# UBTB_MIX__spicesch.net
KiCad netlist of a schematic drawn in EAGLE
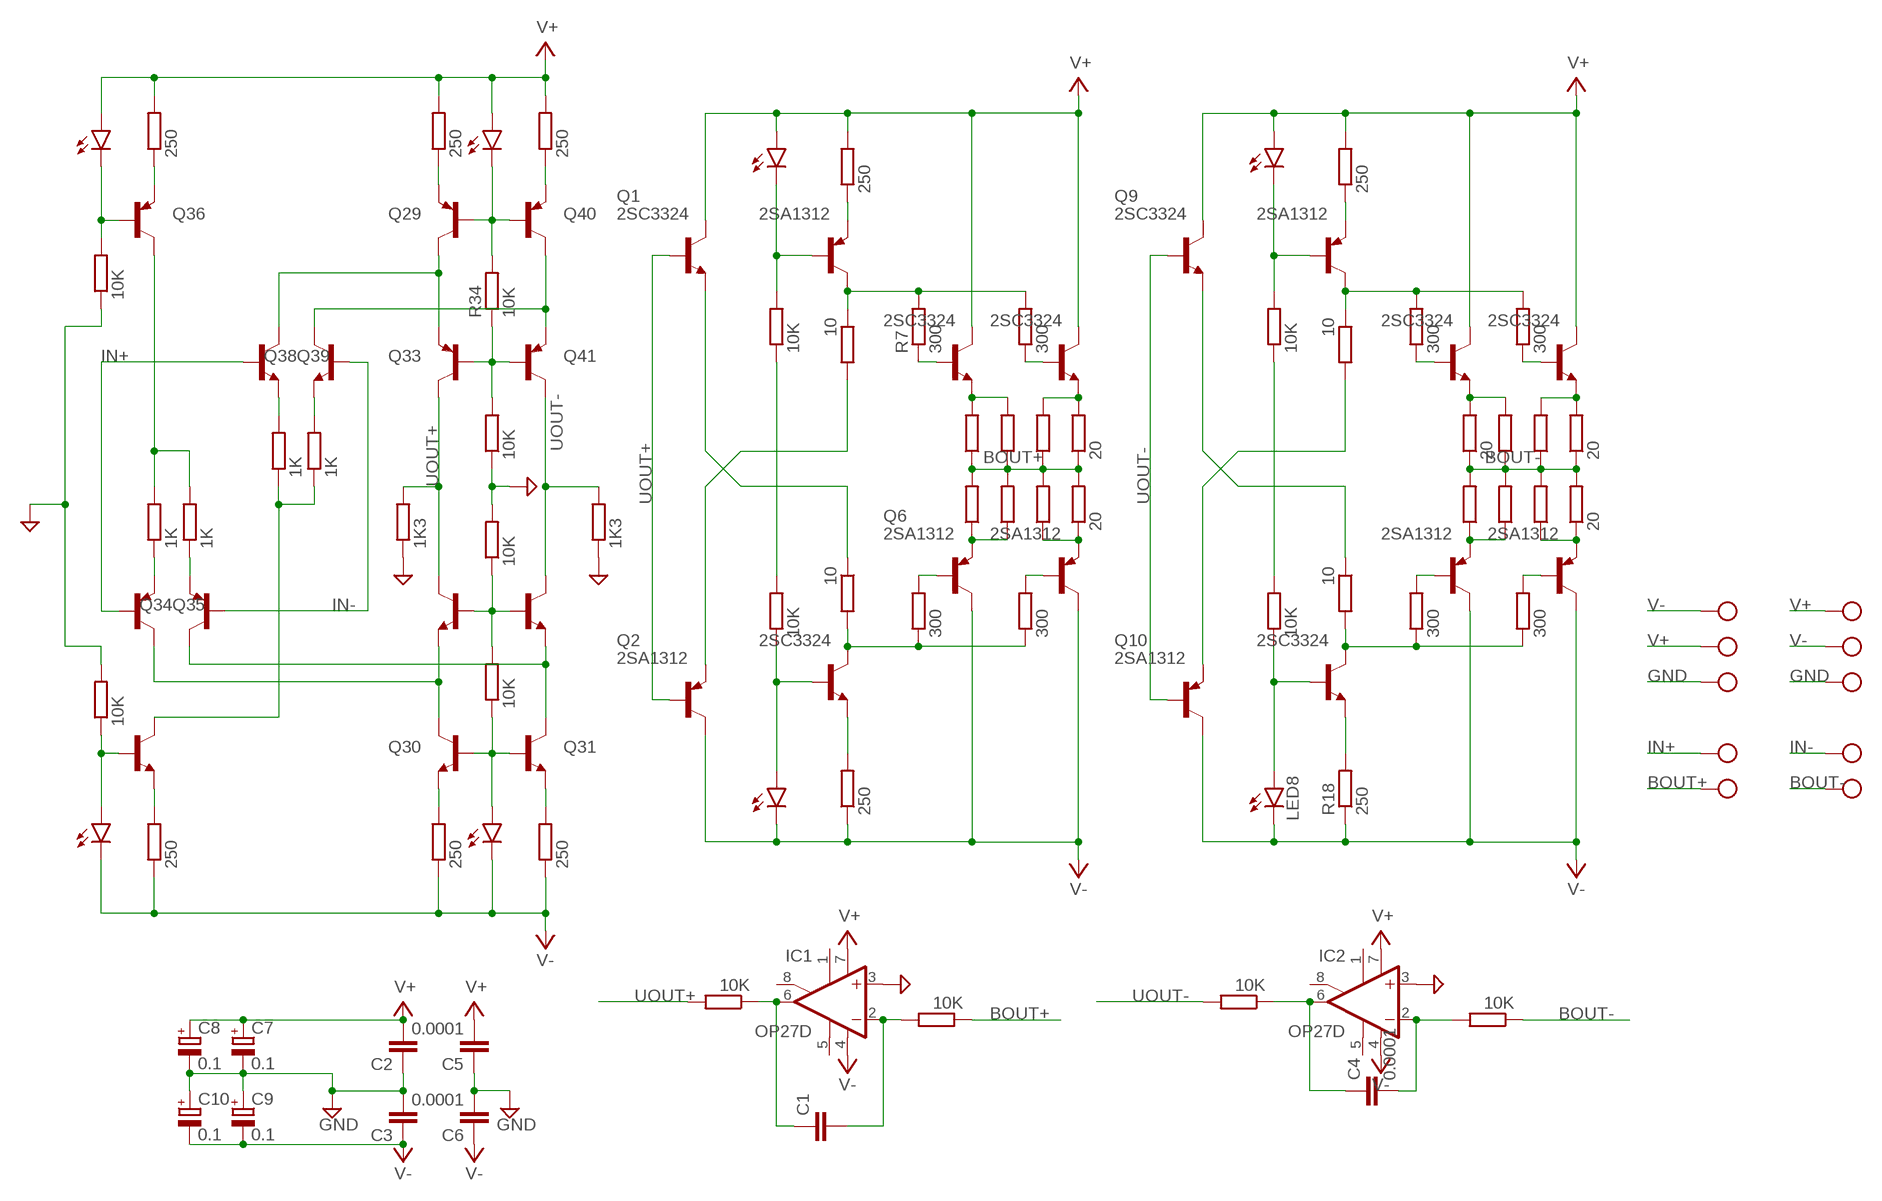
[diagram p0: schematic, sheet 1]

(export (version "E")
  (design (tool "Eeschema 10.0.6"))
  (components
    (comp (ref "C1")
      (value "C-EUC1206")
      (footprint "eagle-import:C1206")
      (fields (field (name "SPICEPREFIX") "C"))
      (libsource (lib "eagle-import") (part "C-EUC1206"))
    )
    (comp (ref "C2")
      (value "C-EUC0805")
      (footprint "eagle-import:C0805")
      (fields (field (name "SPICEPREFIX") "C"))
      (libsource (lib "eagle-import") (part "C-EUC0805"))
    )
    (comp (ref "C3")
      (value "C-EUC0805")
      (footprint "eagle-import:C0805")
      (fields (field (name "SPICEPREFIX") "C"))
      (libsource (lib "eagle-import") (part "C-EUC0805"))
    )
    (comp (ref "C4")
      (value "0.0001")
      (footprint "eagle-import:C1206")
      (fields (field (name "SPICEPREFIX") "C"))
      (libsource (lib "eagle-import") (part "C-EUC1206"))
    )
    (comp (ref "C5")
      (value "0.0001")
      (footprint "eagle-import:C0805")
      (fields (field (name "SPICEPREFIX") "C"))
      (libsource (lib "eagle-import") (part "C-EUC0805"))
    )
    (comp (ref "C6")
      (value "0.0001")
      (footprint "eagle-import:C0805")
      (fields (field (name "SPICEPREFIX") "C"))
      (libsource (lib "eagle-import") (part "C-EUC0805"))
    )
    (comp (ref "C7")
      (value "0.1")
      (footprint "eagle-import:PANASONIC_F")
      (fields (field (name "SPICEPREFIX") "C"))
      (libsource (lib "eagle-import") (part "CPOL-EUF"))
    )
    (comp (ref "C8")
      (value "0.1")
      (footprint "eagle-import:PANASONIC_F")
      (fields (field (name "SPICEPREFIX") "C"))
      (libsource (lib "eagle-import") (part "CPOL-EUF"))
    )
    (comp (ref "C9")
      (value "0.1")
      (footprint "eagle-import:PANASONIC_F")
      (fields (field (name "SPICEPREFIX") "C"))
      (libsource (lib "eagle-import") (part "CPOL-EUF"))
    )
    (comp (ref "C10")
      (value "0.1")
      (footprint "eagle-import:PANASONIC_F")
      (fields (field (name "SPICEPREFIX") "C"))
      (libsource (lib "eagle-import") (part "CPOL-EUF"))
    )
    (comp (ref "IC1")
      (value "OP27D")
      (footprint "eagle-import:SO08")
      (libsource (lib "eagle-import") (part "OP27D"))
    )
    (comp (ref "IC2")
      (value "OP27D")
      (footprint "eagle-import:SO08")
      (libsource (lib "eagle-import") (part "OP27D"))
    )
    (comp (ref "LED1")
      (value "LEDCHIPLED_1206")
      (footprint "eagle-import:CHIPLED_1206")
      (fields (field (name "SPICEPREFIX") "D"))
      (libsource (lib "eagle-import") (part "LEDCHIPLED_1206"))
    )
    (comp (ref "LED2")
      (value "LEDCHIPLED_1206")
      (footprint "eagle-import:CHIPLED_1206")
      (fields (field (name "SPICEPREFIX") "L"))
      (libsource (lib "eagle-import") (part "LEDCHIPLED_1206"))
    )
    (comp (ref "LED3")
      (value "LEDCHIPLED_1206")
      (footprint "eagle-import:CHIPLED_1206")
      (fields (field (name "SPICEPREFIX") "L"))
      (libsource (lib "eagle-import") (part "LEDCHIPLED_1206"))
    )
    (comp (ref "LED4")
      (value "LEDCHIPLED_1206")
      (footprint "eagle-import:CHIPLED_1206")
      (fields (field (name "SPICEPREFIX") "D"))
      (libsource (lib "eagle-import") (part "LEDCHIPLED_1206"))
    )
    (comp (ref "LED5")
      (value "LEDCHIPLED_1206")
      (footprint "eagle-import:CHIPLED_1206")
      (fields (field (name "SPICEPREFIX") "L"))
      (libsource (lib "eagle-import") (part "LEDCHIPLED_1206"))
    )
    (comp (ref "LED6")
      (value "LEDCHIPLED_1206")
      (footprint "eagle-import:CHIPLED_1206")
      (fields (field (name "SPICEPREFIX") "L"))
      (libsource (lib "eagle-import") (part "LEDCHIPLED_1206"))
    )
    (comp (ref "LED7")
      (value "LEDCHIPLED_1206")
      (footprint "eagle-import:CHIPLED_1206")
      (fields (field (name "SPICEPREFIX") "L"))
      (libsource (lib "eagle-import") (part "LEDCHIPLED_1206"))
    )
    (comp (ref "LED8")
      (value "LEDCHIPLED_1206")
      (footprint "eagle-import:CHIPLED_1206")
      (fields (field (name "SPICEPREFIX") "L"))
      (libsource (lib "eagle-import") (part "LEDCHIPLED_1206"))
    )
    (comp (ref "Q1")
      (value "2SC3324")
      (footprint "eagle-import:TRANSISTOR_SOT23-BEC")
      (fields (field (name "SPICEPREFIX") "Q"))
      (libsource (lib "eagle-import") (part "TRANSISTOR_-NPN-SOT23-BECBC846"))
    )
    (comp (ref "Q2")
      (value "2SA1312")
      (footprint "eagle-import:TRANSISTOR_SOT23-BEC")
      (fields (field (name "SPICEPREFIX") "Q"))
      (libsource (lib "eagle-import") (part "TRANSISTOR_-PNP-SOT23-BECBC856B"))
    )
    (comp (ref "Q3")
      (value "2SC3324")
      (footprint "eagle-import:TRANSISTOR_SOT23-BEC")
      (fields (field (name "SPICEPREFIX") "Q"))
      (libsource (lib "eagle-import") (part "TRANSISTOR_-NPN-SOT23-BECBC846"))
    )
    (comp (ref "Q4")
      (value "2SA1312")
      (footprint "eagle-import:TRANSISTOR_SOT23-BEC")
      (fields (field (name "SPICEPREFIX") "Q"))
      (libsource (lib "eagle-import") (part "TRANSISTOR_-PNP-SOT23-BECBC856B"))
    )
    (comp (ref "Q5")
      (value "2SC3324")
      (footprint "eagle-import:TRANSISTOR_SOT23-BEC")
      (fields (field (name "SPICEPREFIX") "Q"))
      (libsource (lib "eagle-import") (part "TRANSISTOR_-NPN-SOT23-BECBC846"))
    )
    (comp (ref "Q6")
      (value "2SA1312")
      (footprint "eagle-import:TRANSISTOR_SOT23-BEC")
      (fields (field (name "SPICEPREFIX") "Q"))
      (libsource (lib "eagle-import") (part "TRANSISTOR_-PNP-SOT23-BECBC856B"))
    )
    (comp (ref "Q7")
      (value "2SA1312")
      (footprint "eagle-import:TRANSISTOR_SOT23-BEC")
      (fields (field (name "SPICEPREFIX") "Q"))
      (libsource (lib "eagle-import") (part "TRANSISTOR_-PNP-SOT23-BECBC856B"))
    )
    (comp (ref "Q8")
      (value "2SC3324")
      (footprint "eagle-import:TRANSISTOR_SOT23-BEC")
      (fields (field (name "SPICEPREFIX") "Q"))
      (libsource (lib "eagle-import") (part "TRANSISTOR_-NPN-SOT23-BECBC846"))
    )
    (comp (ref "Q9")
      (value "2SC3324")
      (footprint "eagle-import:TRANSISTOR_SOT23-BEC")
      (fields (field (name "SPICEPREFIX") "Q"))
      (libsource (lib "eagle-import") (part "TRANSISTOR_-NPN-SOT23-BECBC846"))
    )
    (comp (ref "Q10")
      (value "2SA1312")
      (footprint "eagle-import:TRANSISTOR_SOT23-BEC")
      (fields (field (name "SPICEPREFIX") "Q"))
      (libsource (lib "eagle-import") (part "TRANSISTOR_-PNP-SOT23-BECBC856B"))
    )
    (comp (ref "Q11")
      (value "2SC3324")
      (footprint "eagle-import:TRANSISTOR_SOT23-BEC")
      (fields (field (name "SPICEPREFIX") "Q"))
      (libsource (lib "eagle-import") (part "TRANSISTOR_-NPN-SOT23-BECBC846"))
    )
    (comp (ref "Q12")
      (value "2SA1312")
      (footprint "eagle-import:TRANSISTOR_SOT23-BEC")
      (fields (field (name "SPICEPREFIX") "Q"))
      (libsource (lib "eagle-import") (part "TRANSISTOR_-PNP-SOT23-BECBC856B"))
    )
    (comp (ref "Q13")
      (value "2SC3324")
      (footprint "eagle-import:TRANSISTOR_SOT23-BEC")
      (fields (field (name "SPICEPREFIX") "U"))
      (libsource (lib "eagle-import") (part "TRANSISTOR_-NPN-SOT23-BECBC846"))
    )
    (comp (ref "Q14")
      (value "2SC3324")
      (footprint "eagle-import:TRANSISTOR_SOT23-BEC")
      (fields (field (name "SPICEPREFIX") "Q"))
      (libsource (lib "eagle-import") (part "TRANSISTOR_-NPN-SOT23-BECBC846"))
    )
    (comp (ref "Q15")
      (value "2SA1312")
      (footprint "eagle-import:TRANSISTOR_SOT23-BEC")
      (fields (field (name "SPICEPREFIX") "Q"))
      (libsource (lib "eagle-import") (part "TRANSISTOR_-PNP-SOT23-BECBC856B"))
    )
    (comp (ref "Q16")
      (value "2SA1312")
      (footprint "eagle-import:TRANSISTOR_SOT23-BEC")
      (fields (field (name "SPICEPREFIX") "Q"))
      (libsource (lib "eagle-import") (part "TRANSISTOR_-PNP-SOT23-BECBC856B"))
    )
    (comp (ref "Q26")
      (value "2SC3324")
      (footprint "eagle-import:SOT23")
      (fields (field (name "SPICEPREFIX") "Q"))
      (libsource (lib "eagle-import") (part "BC847SMDC"))
    )
    (comp (ref "Q29")
      (value "2SA1312")
      (footprint "eagle-import:SOT23-BEC")
      (fields (field (name "SPICEPREFIX") "Q"))
      (libsource (lib "eagle-import") (part "BC857SMDC"))
    )
    (comp (ref "Q30")
      (value "2SC3324")
      (footprint "eagle-import:SOT23")
      (fields (field (name "SPICEPREFIX") "Q"))
      (libsource (lib "eagle-import") (part "BC847SMDC"))
    )
    (comp (ref "Q31")
      (value "2SC3324")
      (footprint "eagle-import:SOT23")
      (fields (field (name "SPICEPREFIX") "Q"))
      (libsource (lib "eagle-import") (part "BC847SMDC"))
    )
    (comp (ref "Q32")
      (value "2SC3324")
      (footprint "eagle-import:SOT23")
      (fields (field (name "SPICEPREFIX") "Q"))
      (libsource (lib "eagle-import") (part "BC847SMDC"))
    )
    (comp (ref "Q33")
      (value "2SA1312")
      (footprint "eagle-import:SOT23-BEC")
      (fields (field (name "SPICEPREFIX") "Q"))
      (libsource (lib "eagle-import") (part "BC857SMDC"))
    )
    (comp (ref "Q34")
      (value "2SA1312")
      (footprint "eagle-import:SOT23-BEC")
      (fields (field (name "SPICEPREFIX") "Q"))
      (libsource (lib "eagle-import") (part "BC857SMDC"))
    )
    (comp (ref "Q35")
      (value "2SA1312")
      (footprint "eagle-import:SOT23-BEC")
      (fields (field (name "SPICEPREFIX") "Q"))
      (libsource (lib "eagle-import") (part "BC857SMDC"))
    )
    (comp (ref "Q36")
      (value "2SA1312")
      (footprint "eagle-import:SOT23-BEC")
      (fields (field (name "SPICEPREFIX") "Q"))
      (libsource (lib "eagle-import") (part "BC857SMDC"))
    )
    (comp (ref "Q37")
      (value "2SC3324")
      (footprint "eagle-import:SOT23")
      (fields (field (name "SPICEPREFIX") "Q"))
      (libsource (lib "eagle-import") (part "BC847SMDC"))
    )
    (comp (ref "Q38")
      (value "2SC3324")
      (footprint "eagle-import:SOT23")
      (fields (field (name "SPICEPREFIX") "Q"))
      (libsource (lib "eagle-import") (part "BC847SMDC"))
    )
    (comp (ref "Q39")
      (value "2SC3324")
      (footprint "eagle-import:SOT23")
      (fields (field (name "SPICEPREFIX") "Q"))
      (libsource (lib "eagle-import") (part "BC847SMDC"))
    )
    (comp (ref "Q40")
      (value "2SA1312")
      (footprint "eagle-import:SOT23-BEC")
      (fields (field (name "SPICEPREFIX") "Q"))
      (libsource (lib "eagle-import") (part "BC857SMDC"))
    )
    (comp (ref "Q41")
      (value "2SA1312")
      (footprint "eagle-import:SOT23-BEC")
      (fields (field (name "SPICEPREFIX") "Q"))
      (libsource (lib "eagle-import") (part "BC857SMDC"))
    )
    (comp (ref "R1")
      (value "250")
      (footprint "eagle-import:MINI_MELF-0204W")
      (fields (field (name "SPICEPREFIX") "R"))
      (libsource (lib "eagle-import") (part "R-EU_MELF0204W"))
    )
    (comp (ref "R2")
      (value "250")
      (footprint "eagle-import:MINI_MELF-0204W")
      (fields (field (name "SPICEPREFIX") "R"))
      (libsource (lib "eagle-import") (part "R-EU_MELF0204W"))
    )
    (comp (ref "R3")
      (value "10K")
      (footprint "eagle-import:MINI_MELF-0204W")
      (fields (field (name "SPICEPREFIX") "R"))
      (libsource (lib "eagle-import") (part "R-EU_MELF0204W"))
    )
    (comp (ref "R4")
      (value "10K")
      (footprint "eagle-import:MINI_MELF-0204W")
      (fields (field (name "SPICEPREFIX") "R"))
      (libsource (lib "eagle-import") (part "R-EU_MELF0204W"))
    )
    (comp (ref "R5")
      (value "10")
      (footprint "eagle-import:MINI_MELF-0204W")
      (fields (field (name "SPICEPREFIX") "R"))
      (libsource (lib "eagle-import") (part "R-EU_MELF0204W"))
    )
    (comp (ref "R6")
      (value "10")
      (footprint "eagle-import:MINI_MELF-0204W")
      (fields (field (name "SPICEPREFIX") "R"))
      (libsource (lib "eagle-import") (part "R-EU_MELF0204W"))
    )
    (comp (ref "R7")
      (value "300")
      (footprint "eagle-import:MINI_MELF-0204W")
      (fields (field (name "SPICEPREFIX") "R"))
      (libsource (lib "eagle-import") (part "R-EU_MELF0204W"))
    )
    (comp (ref "R8")
      (value "300")
      (footprint "eagle-import:MINI_MELF-0204W")
      (fields (field (name "SPICEPREFIX") "R"))
      (libsource (lib "eagle-import") (part "R-EU_MELF0204W"))
    )
    (comp (ref "R9")
      (value "300")
      (footprint "eagle-import:MINI_MELF-0204W")
      (fields (field (name "SPICEPREFIX") "R"))
      (libsource (lib "eagle-import") (part "R-EU_MELF0204W"))
    )
    (comp (ref "R10")
      (value "300")
      (footprint "eagle-import:MINI_MELF-0204W")
      (fields (field (name "SPICEPREFIX") "V"))
      (libsource (lib "eagle-import") (part "R-EU_MELF0204W"))
    )
    (comp (ref "R11")
      (value "R-EU_MELF0204W")
      (footprint "eagle-import:MINI_MELF-0204W")
      (fields (field (name "SPICEPREFIX") "R"))
      (libsource (lib "eagle-import") (part "R-EU_MELF0204W"))
    )
    (comp (ref "R12")
      (value "R-EU_MELF0204W")
      (footprint "eagle-import:MINI_MELF-0204W")
      (fields (field (name "SPICEPREFIX") "R"))
      (libsource (lib "eagle-import") (part "R-EU_MELF0204W"))
    )
    (comp (ref "R13")
      (value "20")
      (footprint "eagle-import:MINI_MELF-0204W")
      (fields (field (name "SPICEPREFIX") "R"))
      (libsource (lib "eagle-import") (part "R-EU_MELF0204W"))
    )
    (comp (ref "R14")
      (value "20")
      (footprint "eagle-import:MINI_MELF-0204W")
      (fields (field (name "SPICEPREFIX") "R"))
      (libsource (lib "eagle-import") (part "R-EU_MELF0204W"))
    )
    (comp (ref "R15")
      (value "250")
      (footprint "eagle-import:MINI_MELF-0204W")
      (fields (field (name "SPICEPREFIX") "R"))
      (libsource (lib "eagle-import") (part "R-EU_MELF0204W"))
    )
    (comp (ref "R16")
      (value "10K")
      (footprint "eagle-import:MINI_MELF-0204W")
      (fields (field (name "SPICEPREFIX") "W"))
      (libsource (lib "eagle-import") (part "R-EU_MELF0204W"))
    )
    (comp (ref "R17")
      (value "10K")
      (footprint "eagle-import:MINI_MELF-0204W")
      (fields (field (name "SPICEPREFIX") "R"))
      (libsource (lib "eagle-import") (part "R-EU_MELF0204W"))
    )
    (comp (ref "R18")
      (value "250")
      (footprint "eagle-import:MINI_MELF-0204W")
      (fields (field (name "SPICEPREFIX") "R"))
      (libsource (lib "eagle-import") (part "R-EU_MELF0204W"))
    )
    (comp (ref "R19")
      (value "10K")
      (footprint "eagle-import:MINI_MELF-0204W")
      (fields (field (name "SPICEPREFIX") "R"))
      (libsource (lib "eagle-import") (part "R-EU_MELF0204W"))
    )
    (comp (ref "R20")
      (value "10K")
      (footprint "eagle-import:MINI_MELF-0204W")
      (fields (field (name "SPICEPREFIX") "R"))
      (libsource (lib "eagle-import") (part "R-EU_MELF0204W"))
    )
    (comp (ref "R21")
      (value "10")
      (footprint "eagle-import:MINI_MELF-0204W")
      (fields (field (name "SPICEPREFIX") "R"))
      (libsource (lib "eagle-import") (part "R-EU_MELF0204W"))
    )
    (comp (ref "R22")
      (value "250")
      (footprint "eagle-import:MINI_MELF-0204W")
      (fields (field (name "SPICEPREFIX") "R"))
      (libsource (lib "eagle-import") (part "R-EU_MELF0204W"))
    )
    (comp (ref "R23")
      (value "250")
      (footprint "eagle-import:MINI_MELF-0204W")
      (fields (field (name "SPICEPREFIX") "R"))
      (libsource (lib "eagle-import") (part "R-EU_MELF0204W"))
    )
    (comp (ref "R24")
      (value "10")
      (footprint "eagle-import:MINI_MELF-0204W")
      (fields (field (name "SPICEPREFIX") "W"))
      (libsource (lib "eagle-import") (part "R-EU_MELF0204W"))
    )
    (comp (ref "R25")
      (value "300")
      (footprint "eagle-import:MINI_MELF-0204W")
      (fields (field (name "SPICEPREFIX") "V"))
      (libsource (lib "eagle-import") (part "R-EU_MELF0204W"))
    )
    (comp (ref "R26")
      (value "300")
      (footprint "eagle-import:MINI_MELF-0204W")
      (fields (field (name "SPICEPREFIX") "R"))
      (libsource (lib "eagle-import") (part "R-EU_MELF0204W"))
    )
    (comp (ref "R27")
      (value "300")
      (footprint "eagle-import:MINI_MELF-0204W")
      (fields (field (name "SPICEPREFIX") "V"))
      (libsource (lib "eagle-import") (part "R-EU_MELF0204W"))
    )
    (comp (ref "R28")
      (value "300")
      (footprint "eagle-import:MINI_MELF-0204W")
      (fields (field (name "SPICEPREFIX") "V"))
      (libsource (lib "eagle-import") (part "R-EU_MELF0204W"))
    )
    (comp (ref "R29")
      (value "10K")
      (footprint "eagle-import:MINI_MELF-0204W")
      (fields (field (name "SPICEPREFIX") "R"))
      (libsource (lib "eagle-import") (part "R-EU_MELF0204W"))
    )
    (comp (ref "R30")
      (value "20")
      (footprint "eagle-import:MINI_MELF-0204W")
      (fields (field (name "SPICEPREFIX") "R"))
      (libsource (lib "eagle-import") (part "R-EU_MELF0204W"))
    )
    (comp (ref "R31")
      (value "R-EU_MELF0204W")
      (footprint "eagle-import:MINI_MELF-0204W")
      (fields (field (name "SPICEPREFIX") "R"))
      (libsource (lib "eagle-import") (part "R-EU_MELF0204W"))
    )
    (comp (ref "R32")
      (value "10K")
      (footprint "eagle-import:MINI_MELF-0204W")
      (fields (field (name "SPICEPREFIX") "V"))
      (libsource (lib "eagle-import") (part "R-EU_MELF0204W"))
    )
    (comp (ref "R33")
      (value "10K")
      (footprint "eagle-import:MINI_MELF-0204W")
      (fields (field (name "SPICEPREFIX") "W"))
      (libsource (lib "eagle-import") (part "R-EU_MELF0204W"))
    )
    (comp (ref "R34")
      (value "10K")
      (footprint "eagle-import:MINI_MELF-0204W")
      (fields (field (name "SPICEPREFIX") "R"))
      (libsource (lib "eagle-import") (part "R-EU_MELF0204W"))
    )
    (comp (ref "R35")
      (value "250")
      (footprint "eagle-import:MINI_MELF-0204W")
      (fields (field (name "SPICEPREFIX") "R"))
      (libsource (lib "eagle-import") (part "R-EU_MELF0204W"))
    )
    (comp (ref "R36")
      (value "250")
      (footprint "eagle-import:MINI_MELF-0204W")
      (fields (field (name "SPICEPREFIX") "R"))
      (libsource (lib "eagle-import") (part "R-EU_MELF0204W"))
    )
    (comp (ref "R37")
      (value "1K3")
      (footprint "eagle-import:MINI_MELF-0204W")
      (fields (field (name "SPICEPREFIX") "R"))
      (libsource (lib "eagle-import") (part "R-EU_MELF0204W"))
    )
    (comp (ref "R38")
      (value "1K3")
      (footprint "eagle-import:MINI_MELF-0204W")
      (fields (field (name "SPICEPREFIX") "R"))
      (libsource (lib "eagle-import") (part "R-EU_MELF0204W"))
    )
    (comp (ref "R39")
      (value "1K")
      (footprint "eagle-import:MINI_MELF-0204W")
      (fields (field (name "SPICEPREFIX") "R"))
      (libsource (lib "eagle-import") (part "R-EU_MELF0204W"))
    )
    (comp (ref "R40")
      (value "1K")
      (footprint "eagle-import:MINI_MELF-0204W")
      (fields (field (name "SPICEPREFIX") "R"))
      (libsource (lib "eagle-import") (part "R-EU_MELF0204W"))
    )
    (comp (ref "R41")
      (value "1K")
      (footprint "eagle-import:MINI_MELF-0204W")
      (fields (field (name "SPICEPREFIX") "R"))
      (libsource (lib "eagle-import") (part "R-EU_MELF0204W"))
    )
    (comp (ref "R42")
      (value "1K")
      (footprint "eagle-import:MINI_MELF-0204W")
      (fields (field (name "SPICEPREFIX") "R"))
      (libsource (lib "eagle-import") (part "R-EU_MELF0204W"))
    )
    (comp (ref "R43")
      (value "250")
      (footprint "eagle-import:MINI_MELF-0204W")
      (fields (field (name "SPICEPREFIX") "R"))
      (libsource (lib "eagle-import") (part "R-EU_MELF0204W"))
    )
    (comp (ref "R44")
      (value "250")
      (footprint "eagle-import:MINI_MELF-0204W")
      (fields (field (name "SPICEPREFIX") "R"))
      (libsource (lib "eagle-import") (part "R-EU_MELF0204W"))
    )
    (comp (ref "R45")
      (value "10K")
      (footprint "eagle-import:MINI_MELF-0204W")
      (fields (field (name "SPICEPREFIX") "R"))
      (libsource (lib "eagle-import") (part "R-EU_MELF0204W"))
    )
    (comp (ref "R46")
      (value "10K")
      (footprint "eagle-import:MINI_MELF-0204W")
      (fields (field (name "SPICEPREFIX") "R"))
      (libsource (lib "eagle-import") (part "R-EU_MELF0204W"))
    )
    (comp (ref "R47")
      (value "20")
      (footprint "eagle-import:MINI_MELF-0204W")
      (fields (field (name "SPICEPREFIX") "R"))
      (libsource (lib "eagle-import") (part "R-EU_MELF0204W"))
    )
    (comp (ref "R48")
      (value "10K")
      (footprint "eagle-import:MINI_MELF-0204W")
      (fields (field (name "SPICEPREFIX") "V"))
      (libsource (lib "eagle-import") (part "R-EU_MELF0204W"))
    )
    (comp (ref "R49")
      (value "20")
      (footprint "eagle-import:MINI_MELF-0204W")
      (fields (field (name "SPICEPREFIX") "R"))
      (libsource (lib "eagle-import") (part "R-EU_MELF0204W"))
    )
    (comp (ref "R50")
      (value "R-EU_MELF0204W")
      (footprint "eagle-import:MINI_MELF-0204W")
      (fields (field (name "SPICEPREFIX") "R"))
      (libsource (lib "eagle-import") (part "R-EU_MELF0204W"))
    )
    (comp (ref "R51")
      (value "10K")
      (footprint "eagle-import:MINI_MELF-0204W")
      (fields (field (name "SPICEPREFIX") "R"))
      (libsource (lib "eagle-import") (part "R-EU_MELF0204W"))
    )
    (comp (ref "R52")
      (value "R-EU_MELF0204W")
      (footprint "eagle-import:MINI_MELF-0204W")
      (fields (field (name "SPICEPREFIX") "R"))
      (libsource (lib "eagle-import") (part "R-EU_MELF0204W"))
    )
    (comp (ref "R53")
      (value "R-EU_MELF0204W")
      (footprint "eagle-import:MINI_MELF-0204W")
      (fields (field (name "SPICEPREFIX") "R"))
      (libsource (lib "eagle-import") (part "R-EU_MELF0204W"))
    )
    (comp (ref "R54")
      (value "R-EU_MELF0204W")
      (footprint "eagle-import:MINI_MELF-0204W")
      (fields (field (name "SPICEPREFIX") "R"))
      (libsource (lib "eagle-import") (part "R-EU_MELF0204W"))
    )
    (comp (ref "R55")
      (value "R-EU_MELF0204W")
      (footprint "eagle-import:MINI_MELF-0204W")
      (fields (field (name "SPICEPREFIX") "R"))
      (libsource (lib "eagle-import") (part "R-EU_MELF0204W"))
    )
    (comp (ref "R56")
      (value "R-EU_MELF0204W")
      (footprint "eagle-import:MINI_MELF-0204W")
      (fields (field (name "SPICEPREFIX") "R"))
      (libsource (lib "eagle-import") (part "R-EU_MELF0204W"))
    )
    (comp (ref "R57")
      (value "R-EU_MELF0204W")
      (footprint "eagle-import:MINI_MELF-0204W")
      (fields (field (name "SPICEPREFIX") "R"))
      (libsource (lib "eagle-import") (part "R-EU_MELF0204W"))
    )
    (comp (ref "R58")
      (value "R-EU_MELF0204W")
      (footprint "eagle-import:MINI_MELF-0204W")
      (fields (field (name "SPICEPREFIX") "R"))
      (libsource (lib "eagle-import") (part "R-EU_MELF0204W"))
    )
    (comp (ref "X1")
      (value "CON-PHOENIX-508_MKDSN1,5/3-5,08")
      (footprint "eagle-import:CON-PHOENIX-508_MKDSN1,5_3-5,08")
      (fields (field (name "SPICEPREFIX") "X"))
      (libsource (lib "eagle-import") (part "CON-PHOENIX-508_MKDSN1,5/3-5,08"))
    )
    (comp (ref "X2")
      (value "CON-PHOENIX-508_MKDSN1,5/3-5,08")
      (footprint "eagle-import:CON-PHOENIX-508_MKDSN1,5_3-5,08")
      (fields (field (name "SPICEPREFIX") "X"))
      (libsource (lib "eagle-import") (part "CON-PHOENIX-508_MKDSN1,5/3-5,08"))
    )
    (comp (ref "X3")
      (value "CON-PHOENIX-508_MKDSN1,5/2-5,08")
      (footprint "eagle-import:CON-PHOENIX-508_MKDSN1,5_2-5,08")
      (fields (field (name "SPICEPREFIX") "X"))
      (libsource (lib "eagle-import") (part "CON-PHOENIX-508_MKDSN1,5/2-5,08"))
    )
    (comp (ref "X4")
      (value "CON-PHOENIX-508_MKDSN1,5/2-5,08")
      (footprint "eagle-import:CON-PHOENIX-508_MKDSN1,5_2-5,08")
      (fields (field (name "SPICEPREFIX") "X"))
      (libsource (lib "eagle-import") (part "CON-PHOENIX-508_MKDSN1,5/2-5,08"))
    )
  )
  (nets
    (net (code "1") (name "/BOUT+") (class "Default")
      (node (ref "R11") (pin "1") (pinfunction "1_1") (pintype "passive"))
      (node (ref "R12") (pin "2") (pinfunction "2_2") (pintype "passive"))
      (node (ref "R13") (pin "1") (pinfunction "1_1") (pintype "passive"))
      (node (ref "R14") (pin "2") (pinfunction "2_2") (pintype "passive"))
      (node (ref "R17") (pin "1") (pinfunction "1_1") (pintype "passive"))
      (node (ref "R50") (pin "1") (pinfunction "1_1") (pintype "passive"))
      (node (ref "R52") (pin "1") (pinfunction "1_1") (pintype "passive"))
      (node (ref "R53") (pin "2") (pinfunction "2_2") (pintype "passive"))
      (node (ref "R54") (pin "2") (pinfunction "2_2") (pintype "passive"))
      (node (ref "X3") (pin "2") (pinfunction "KL_2") (pintype "passive"))
    )
    (net (code "2") (name "/BOUT-") (class "Default")
      (node (ref "R30") (pin "1") (pinfunction "1_1") (pintype "passive"))
      (node (ref "R31") (pin "2") (pinfunction "2_2") (pintype "passive"))
      (node (ref "R47") (pin "1") (pinfunction "1_1") (pintype "passive"))
      (node (ref "R48") (pin "1") (pinfunction "1_1") (pintype "passive"))
      (node (ref "R49") (pin "2") (pinfunction "2_2") (pintype "passive"))
      (node (ref "R55") (pin "1") (pinfunction "1_1") (pintype "passive"))
      (node (ref "R56") (pin "1") (pinfunction "1_1") (pintype "passive"))
      (node (ref "R57") (pin "2") (pinfunction "2_2") (pintype "passive"))
      (node (ref "R58") (pin "2") (pinfunction "2_2") (pintype "passive"))
      (node (ref "X4") (pin "2") (pinfunction "KL_2") (pintype "passive"))
    )
    (net (code "3") (name "/IN+") (class "Default")
      (node (ref "Q35") (pin "B") (pinfunction "B_B") (pintype "passive"))
      (node (ref "Q39") (pin "1") (pinfunction "B_1") (pintype "passive"))
      (node (ref "X3") (pin "1") (pinfunction "KL_1") (pintype "passive"))
    )
    (net (code "4") (name "/IN-") (class "Default")
      (node (ref "Q34") (pin "B") (pinfunction "B_B") (pintype "passive"))
      (node (ref "Q38") (pin "1") (pinfunction "B_1") (pintype "passive"))
      (node (ref "X4") (pin "1") (pinfunction "KL_1") (pintype "passive"))
    )
    (net (code "5") (name "/UOUT+") (class "Default")
      (node (ref "Q1") (pin "B") (pinfunction "B_B") (pintype "passive"))
      (node (ref "Q2") (pin "B") (pinfunction "B_B") (pintype "passive"))
      (node (ref "Q33") (pin "C") (pinfunction "C_C") (pintype "passive"))
      (node (ref "Q37") (pin "3") (pinfunction "C_3") (pintype "passive"))
      (node (ref "R16") (pin "2") (pinfunction "2_2") (pintype "passive"))
      (node (ref "R37") (pin "2") (pinfunction "2_2") (pintype "passive"))
    )
    (net (code "6") (name "/UOUT-") (class "Default")
      (node (ref "Q10") (pin "B") (pinfunction "B_B") (pintype "passive"))
      (node (ref "Q32") (pin "3") (pinfunction "C_3") (pintype "passive"))
      (node (ref "Q41") (pin "C") (pinfunction "C_C") (pintype "passive"))
      (node (ref "Q9") (pin "B") (pinfunction "B_B") (pintype "passive"))
      (node (ref "R38") (pin "2") (pinfunction "2_2") (pintype "passive"))
      (node (ref "R51") (pin "2") (pinfunction "2_2") (pintype "passive"))
    )
    (net (code "7") (name "GND") (class "Default")
      (node (ref "C10") (pin "+") (pinfunction "+_+") (pintype "passive"))
      (node (ref "C2") (pin "1") (pinfunction "1_1") (pintype "passive"))
      (node (ref "C3") (pin "2") (pinfunction "2_2") (pintype "passive"))
      (node (ref "C5") (pin "1") (pinfunction "1_1") (pintype "passive"))
      (node (ref "C6") (pin "2") (pinfunction "2_2") (pintype "passive"))
      (node (ref "C7") (pin "-") (pinfunction "-_-") (pintype "passive"))
      (node (ref "C8") (pin "-") (pinfunction "-_-") (pintype "passive"))
      (node (ref "C9") (pin "+") (pinfunction "+_+") (pintype "passive"))
      (node (ref "IC1") (pin "3") (pinfunction "+IN_3") (pintype "input"))
      (node (ref "IC2") (pin "3") (pinfunction "+IN_3") (pintype "input"))
      (node (ref "R32") (pin "2") (pinfunction "2_2") (pintype "passive"))
      (node (ref "R33") (pin "1") (pinfunction "1_1") (pintype "passive"))
      (node (ref "R37") (pin "1") (pinfunction "1_1") (pintype "passive"))
      (node (ref "R38") (pin "1") (pinfunction "1_1") (pintype "passive"))
      (node (ref "R45") (pin "1") (pinfunction "1_1") (pintype "passive"))
      (node (ref "R46") (pin "2") (pinfunction "2_2") (pintype "passive"))
      (node (ref "X1") (pin "3") (pinfunction "KL_3") (pintype "passive"))
      (node (ref "X2") (pin "3") (pinfunction "KL_3") (pintype "passive"))
    )
    (net (code "8") (name "Net-(IC1--IN)") (class "Default")
      (node (ref "C1") (pin "2") (pinfunction "2_2") (pintype "passive"))
      (node (ref "IC1") (pin "2") (pinfunction "-IN_2") (pintype "input"))
      (node (ref "R17") (pin "2") (pinfunction "2_2") (pintype "passive"))
    )
    (net (code "9") (name "Net-(IC1-OUT)") (class "Default")
      (node (ref "C1") (pin "1") (pinfunction "1_1") (pintype "passive"))
      (node (ref "IC1") (pin "6") (pinfunction "OUT_6") (pintype "output"))
      (node (ref "R16") (pin "1") (pinfunction "1_1") (pintype "passive"))
    )
    (net (code "10") (name "Net-(IC2--IN)") (class "Default")
      (node (ref "C4") (pin "2") (pinfunction "2_2") (pintype "passive"))
      (node (ref "IC2") (pin "2") (pinfunction "-IN_2") (pintype "input"))
      (node (ref "R48") (pin "2") (pinfunction "2_2") (pintype "passive"))
    )
    (net (code "11") (name "Net-(IC2-OUT)") (class "Default")
      (node (ref "C4") (pin "1") (pinfunction "1_1") (pintype "passive"))
      (node (ref "IC2") (pin "6") (pinfunction "OUT_6") (pintype "output"))
      (node (ref "R51") (pin "1") (pinfunction "1_1") (pintype "passive"))
    )
    (net (code "12") (name "Net-(LED2-PadC)") (class "Default")
      (node (ref "LED2") (pin "C") (pinfunction "C_C") (pintype "passive"))
      (node (ref "Q29") (pin "B") (pinfunction "B_B") (pintype "passive"))
      (node (ref "Q40") (pin "B") (pinfunction "B_B") (pintype "passive"))
      (node (ref "R34") (pin "2") (pinfunction "2_2") (pintype "passive"))
    )
    (net (code "13") (name "Net-(LED3-PadC)") (class "Default")
      (node (ref "LED3") (pin "C") (pinfunction "C_C") (pintype "passive"))
      (node (ref "Q36") (pin "B") (pinfunction "B_B") (pintype "passive"))
      (node (ref "R45") (pin "2") (pinfunction "2_2") (pintype "passive"))
    )
    (net (code "14") (name "Net-(LED5-PadC)") (class "Default")
      (node (ref "LED5") (pin "C") (pinfunction "C_C") (pintype "passive"))
      (node (ref "Q4") (pin "B") (pinfunction "B_B") (pintype "passive"))
      (node (ref "R3") (pin "2") (pinfunction "2_2") (pintype "passive"))
    )
    (net (code "15") (name "Net-(LED6-PadA)") (class "Default")
      (node (ref "LED6") (pin "A") (pinfunction "A_A") (pintype "passive"))
      (node (ref "Q3") (pin "B") (pinfunction "B_B") (pintype "passive"))
      (node (ref "R4") (pin "1") (pinfunction "1_1") (pintype "passive"))
    )
    (net (code "16") (name "Net-(LED7-PadC)") (class "Default")
      (node (ref "LED7") (pin "C") (pinfunction "C_C") (pintype "passive"))
      (node (ref "Q12") (pin "B") (pinfunction "B_B") (pintype "passive"))
      (node (ref "R19") (pin "2") (pinfunction "2_2") (pintype "passive"))
    )
    (net (code "17") (name "Net-(LED8-PadA)") (class "Default")
      (node (ref "LED8") (pin "A") (pinfunction "A_A") (pintype "passive"))
      (node (ref "Q11") (pin "B") (pinfunction "B_B") (pintype "passive"))
      (node (ref "R20") (pin "1") (pinfunction "1_1") (pintype "passive"))
    )
    (net (code "18") (name "Net-(Q1-PadE)") (class "Default")
      (node (ref "Q1") (pin "E") (pinfunction "E_E") (pintype "passive"))
      (node (ref "R6") (pin "1") (pinfunction "1_1") (pintype "passive"))
    )
    (net (code "19") (name "Net-(Q2-PadE)") (class "Default")
      (node (ref "Q2") (pin "E") (pinfunction "E_E") (pintype "passive"))
      (node (ref "R5") (pin "2") (pinfunction "2_2") (pintype "passive"))
    )
    (net (code "20") (name "Net-(Q3-PadC)") (class "Default")
      (node (ref "Q3") (pin "C") (pinfunction "C_C") (pintype "passive"))
      (node (ref "R6") (pin "2") (pinfunction "2_2") (pintype "passive"))
      (node (ref "R8") (pin "1") (pinfunction "1_1") (pintype "passive"))
      (node (ref "R9") (pin "1") (pinfunction "1_1") (pintype "passive"))
    )
    (net (code "21") (name "Net-(Q3-PadE)") (class "Default")
      (node (ref "Q3") (pin "E") (pinfunction "E_E") (pintype "passive"))
      (node (ref "R2") (pin "2") (pinfunction "2_2") (pintype "passive"))
    )
    (net (code "22") (name "Net-(Q4-PadC)") (class "Default")
      (node (ref "Q4") (pin "C") (pinfunction "C_C") (pintype "passive"))
      (node (ref "R10") (pin "2") (pinfunction "2_2") (pintype "passive"))
      (node (ref "R5") (pin "1") (pinfunction "1_1") (pintype "passive"))
      (node (ref "R7") (pin "2") (pinfunction "2_2") (pintype "passive"))
    )
    (net (code "23") (name "Net-(Q4-PadE)") (class "Default")
      (node (ref "Q4") (pin "E") (pinfunction "E_E") (pintype "passive"))
      (node (ref "R1") (pin "1") (pinfunction "1_1") (pintype "passive"))
    )
    (net (code "24") (name "Net-(Q5-PadB)") (class "Default")
      (node (ref "Q5") (pin "B") (pinfunction "B_B") (pintype "passive"))
      (node (ref "R7") (pin "1") (pinfunction "1_1") (pintype "passive"))
    )
    (net (code "25") (name "Net-(Q5-PadE)") (class "Default")
      (node (ref "Q5") (pin "E") (pinfunction "E_E") (pintype "passive"))
      (node (ref "R11") (pin "2") (pinfunction "2_2") (pintype "passive"))
      (node (ref "R50") (pin "2") (pinfunction "2_2") (pintype "passive"))
    )
    (net (code "26") (name "Net-(Q6-PadB)") (class "Default")
      (node (ref "Q6") (pin "B") (pinfunction "B_B") (pintype "passive"))
      (node (ref "R8") (pin "2") (pinfunction "2_2") (pintype "passive"))
    )
    (net (code "27") (name "Net-(Q6-PadE)") (class "Default")
      (node (ref "Q6") (pin "E") (pinfunction "E_E") (pintype "passive"))
      (node (ref "R12") (pin "1") (pinfunction "1_1") (pintype "passive"))
      (node (ref "R53") (pin "1") (pinfunction "1_1") (pintype "passive"))
    )
    (net (code "28") (name "Net-(Q7-PadB)") (class "Default")
      (node (ref "Q7") (pin "B") (pinfunction "B_B") (pintype "passive"))
      (node (ref "R9") (pin "2") (pinfunction "2_2") (pintype "passive"))
    )
    (net (code "29") (name "Net-(Q7-PadE)") (class "Default")
      (node (ref "Q7") (pin "E") (pinfunction "E_E") (pintype "passive"))
      (node (ref "R14") (pin "1") (pinfunction "1_1") (pintype "passive"))
      (node (ref "R54") (pin "1") (pinfunction "1_1") (pintype "passive"))
    )
    (net (code "30") (name "Net-(Q8-PadB)") (class "Default")
      (node (ref "Q8") (pin "B") (pinfunction "B_B") (pintype "passive"))
      (node (ref "R10") (pin "1") (pinfunction "1_1") (pintype "passive"))
    )
    (net (code "31") (name "Net-(Q8-PadE)") (class "Default")
      (node (ref "Q8") (pin "E") (pinfunction "E_E") (pintype "passive"))
      (node (ref "R13") (pin "2") (pinfunction "2_2") (pintype "passive"))
      (node (ref "R52") (pin "2") (pinfunction "2_2") (pintype "passive"))
    )
    (net (code "32") (name "Net-(Q9-PadE)") (class "Default")
      (node (ref "Q9") (pin "E") (pinfunction "E_E") (pintype "passive"))
      (node (ref "R24") (pin "1") (pinfunction "1_1") (pintype "passive"))
    )
    (net (code "33") (name "Net-(Q10-PadE)") (class "Default")
      (node (ref "Q10") (pin "E") (pinfunction "E_E") (pintype "passive"))
      (node (ref "R21") (pin "2") (pinfunction "2_2") (pintype "passive"))
    )
    (net (code "34") (name "Net-(Q11-PadC)") (class "Default")
      (node (ref "Q11") (pin "C") (pinfunction "C_C") (pintype "passive"))
      (node (ref "R24") (pin "2") (pinfunction "2_2") (pintype "passive"))
      (node (ref "R26") (pin "1") (pinfunction "1_1") (pintype "passive"))
      (node (ref "R27") (pin "1") (pinfunction "1_1") (pintype "passive"))
    )
    (net (code "35") (name "Net-(Q11-PadE)") (class "Default")
      (node (ref "Q11") (pin "E") (pinfunction "E_E") (pintype "passive"))
      (node (ref "R18") (pin "2") (pinfunction "2_2") (pintype "passive"))
    )
    (net (code "36") (name "Net-(Q12-PadC)") (class "Default")
      (node (ref "Q12") (pin "C") (pinfunction "C_C") (pintype "passive"))
      (node (ref "R21") (pin "1") (pinfunction "1_1") (pintype "passive"))
      (node (ref "R25") (pin "2") (pinfunction "2_2") (pintype "passive"))
      (node (ref "R28") (pin "2") (pinfunction "2_2") (pintype "passive"))
    )
    (net (code "37") (name "Net-(Q12-PadE)") (class "Default")
      (node (ref "Q12") (pin "E") (pinfunction "E_E") (pintype "passive"))
      (node (ref "R15") (pin "1") (pinfunction "1_1") (pintype "passive"))
    )
    (net (code "38") (name "Net-(Q13-PadB)") (class "Default")
      (node (ref "Q13") (pin "B") (pinfunction "B_B") (pintype "passive"))
      (node (ref "R25") (pin "1") (pinfunction "1_1") (pintype "passive"))
    )
    (net (code "39") (name "Net-(Q13-PadE)") (class "Default")
      (node (ref "Q13") (pin "E") (pinfunction "E_E") (pintype "passive"))
      (node (ref "R30") (pin "2") (pinfunction "2_2") (pintype "passive"))
      (node (ref "R55") (pin "2") (pinfunction "2_2") (pintype "passive"))
    )
    (net (code "40") (name "Net-(Q14-PadB)") (class "Default")
      (node (ref "Q14") (pin "B") (pinfunction "B_B") (pintype "passive"))
      (node (ref "R28") (pin "1") (pinfunction "1_1") (pintype "passive"))
    )
    (net (code "41") (name "Net-(Q14-PadE)") (class "Default")
      (node (ref "Q14") (pin "E") (pinfunction "E_E") (pintype "passive"))
      (node (ref "R47") (pin "2") (pinfunction "2_2") (pintype "passive"))
      (node (ref "R56") (pin "2") (pinfunction "2_2") (pintype "passive"))
    )
    (net (code "42") (name "Net-(Q15-PadB)") (class "Default")
      (node (ref "Q15") (pin "B") (pinfunction "B_B") (pintype "passive"))
      (node (ref "R26") (pin "2") (pinfunction "2_2") (pintype "passive"))
    )
    (net (code "43") (name "Net-(Q15-PadE)") (class "Default")
      (node (ref "Q15") (pin "E") (pinfunction "E_E") (pintype "passive"))
      (node (ref "R31") (pin "1") (pinfunction "1_1") (pintype "passive"))
      (node (ref "R58") (pin "1") (pinfunction "1_1") (pintype "passive"))
    )
    (net (code "44") (name "Net-(Q16-PadB)") (class "Default")
      (node (ref "Q16") (pin "B") (pinfunction "B_B") (pintype "passive"))
      (node (ref "R27") (pin "2") (pinfunction "2_2") (pintype "passive"))
    )
    (net (code "45") (name "Net-(Q16-PadE)") (class "Default")
      (node (ref "Q16") (pin "E") (pinfunction "E_E") (pintype "passive"))
      (node (ref "R49") (pin "1") (pinfunction "1_1") (pintype "passive"))
      (node (ref "R57") (pin "1") (pinfunction "1_1") (pintype "passive"))
    )
    (net (code "46") (name "Net-(Q26-B)") (class "Default")
      (node (ref "LED4") (pin "A") (pinfunction "A_A") (pintype "passive"))
      (node (ref "Q26") (pin "1") (pinfunction "B_1") (pintype "passive"))
      (node (ref "R46") (pin "1") (pinfunction "1_1") (pintype "passive"))
    )
    (net (code "47") (name "Net-(Q26-C)") (class "Default")
      (node (ref "Q26") (pin "3") (pinfunction "C_3") (pintype "passive"))
      (node (ref "R39") (pin "1") (pinfunction "1_1") (pintype "passive"))
      (node (ref "R40") (pin "1") (pinfunction "1_1") (pintype "passive"))
    )
    (net (code "48") (name "Net-(Q26-E)") (class "Default")
      (node (ref "Q26") (pin "2") (pinfunction "E_2") (pintype "passive"))
      (node (ref "R44") (pin "2") (pinfunction "2_2") (pintype "passive"))
    )
    (net (code "49") (name "Net-(Q29-PadE)") (class "Default")
      (node (ref "Q29") (pin "E") (pinfunction "E_E") (pintype "passive"))
      (node (ref "R35") (pin "1") (pinfunction "1_1") (pintype "passive"))
    )
    (net (code "50") (name "Net-(Q30-B)") (class "Default")
      (node (ref "LED1") (pin "A") (pinfunction "A_A") (pintype "passive"))
      (node (ref "Q30") (pin "1") (pinfunction "B_1") (pintype "passive"))
      (node (ref "Q31") (pin "1") (pinfunction "B_1") (pintype "passive"))
      (node (ref "R29") (pin "1") (pinfunction "1_1") (pintype "passive"))
    )
    (net (code "51") (name "Net-(Q30-C)") (class "Default")
      (node (ref "Q30") (pin "3") (pinfunction "C_3") (pintype "passive"))
      (node (ref "Q35") (pin "C") (pinfunction "C_C") (pintype "passive"))
      (node (ref "Q37") (pin "2") (pinfunction "E_2") (pintype "passive"))
    )
    (net (code "52") (name "Net-(Q30-E)") (class "Default")
      (node (ref "Q30") (pin "2") (pinfunction "E_2") (pintype "passive"))
      (node (ref "R22") (pin "2") (pinfunction "2_2") (pintype "passive"))
    )
    (net (code "53") (name "Net-(Q31-C)") (class "Default")
      (node (ref "Q31") (pin "3") (pinfunction "C_3") (pintype "passive"))
      (node (ref "Q32") (pin "2") (pinfunction "E_2") (pintype "passive"))
      (node (ref "Q34") (pin "C") (pinfunction "C_C") (pintype "passive"))
    )
    (net (code "54") (name "Net-(Q31-E)") (class "Default")
      (node (ref "Q31") (pin "2") (pinfunction "E_2") (pintype "passive"))
      (node (ref "R23") (pin "2") (pinfunction "2_2") (pintype "passive"))
    )
    (net (code "55") (name "Net-(Q32-B)") (class "Default")
      (node (ref "Q32") (pin "1") (pinfunction "B_1") (pintype "passive"))
      (node (ref "Q37") (pin "1") (pinfunction "B_1") (pintype "passive"))
      (node (ref "R29") (pin "2") (pinfunction "2_2") (pintype "passive"))
      (node (ref "R32") (pin "1") (pinfunction "1_1") (pintype "passive"))
    )
    (net (code "56") (name "Net-(Q33-PadB)") (class "Default")
      (node (ref "Q33") (pin "B") (pinfunction "B_B") (pintype "passive"))
      (node (ref "Q41") (pin "B") (pinfunction "B_B") (pintype "passive"))
      (node (ref "R33") (pin "2") (pinfunction "2_2") (pintype "passive"))
      (node (ref "R34") (pin "1") (pinfunction "1_1") (pintype "passive"))
    )
    (net (code "57") (name "Net-(Q34-PadE)") (class "Default")
      (node (ref "Q34") (pin "E") (pinfunction "E_E") (pintype "passive"))
      (node (ref "R42") (pin "1") (pinfunction "1_1") (pintype "passive"))
    )
    (net (code "58") (name "Net-(Q35-PadE)") (class "Default")
      (node (ref "Q35") (pin "E") (pinfunction "E_E") (pintype "passive"))
      (node (ref "R41") (pin "1") (pinfunction "1_1") (pintype "passive"))
    )
    (net (code "59") (name "Net-(Q36-PadC)") (class "Default")
      (node (ref "Q36") (pin "C") (pinfunction "C_C") (pintype "passive"))
      (node (ref "R41") (pin "2") (pinfunction "2_2") (pintype "passive"))
      (node (ref "R42") (pin "2") (pinfunction "2_2") (pintype "passive"))
    )
    (net (code "60") (name "Net-(Q36-PadE)") (class "Default")
      (node (ref "Q36") (pin "E") (pinfunction "E_E") (pintype "passive"))
      (node (ref "R43") (pin "1") (pinfunction "1_1") (pintype "passive"))
    )
    (net (code "61") (name "Net-(Q38-C)") (class "Default")
      (node (ref "Q38") (pin "3") (pinfunction "C_3") (pintype "passive"))
      (node (ref "Q40") (pin "C") (pinfunction "C_C") (pintype "passive"))
      (node (ref "Q41") (pin "E") (pinfunction "E_E") (pintype "passive"))
    )
    (net (code "62") (name "Net-(Q38-E)") (class "Default")
      (node (ref "Q38") (pin "2") (pinfunction "E_2") (pintype "passive"))
      (node (ref "R40") (pin "2") (pinfunction "2_2") (pintype "passive"))
    )
    (net (code "63") (name "Net-(Q39-C)") (class "Default")
      (node (ref "Q29") (pin "C") (pinfunction "C_C") (pintype "passive"))
      (node (ref "Q33") (pin "E") (pinfunction "E_E") (pintype "passive"))
      (node (ref "Q39") (pin "3") (pinfunction "C_3") (pintype "passive"))
    )
    (net (code "64") (name "Net-(Q39-E)") (class "Default")
      (node (ref "Q39") (pin "2") (pinfunction "E_2") (pintype "passive"))
      (node (ref "R39") (pin "2") (pinfunction "2_2") (pintype "passive"))
    )
    (net (code "65") (name "Net-(Q40-PadE)") (class "Default")
      (node (ref "Q40") (pin "E") (pinfunction "E_E") (pintype "passive"))
      (node (ref "R36") (pin "1") (pinfunction "1_1") (pintype "passive"))
    )
    (net (code "66") (name "Net-(R3-Pad1)") (class "Default")
      (node (ref "R3") (pin "1") (pinfunction "1_1") (pintype "passive"))
      (node (ref "R4") (pin "2") (pinfunction "2_2") (pintype "passive"))
    )
    (net (code "67") (name "Net-(R19-Pad1)") (class "Default")
      (node (ref "R19") (pin "1") (pinfunction "1_1") (pintype "passive"))
      (node (ref "R20") (pin "2") (pinfunction "2_2") (pintype "passive"))
    )
    (net (code "68") (name "V+") (class "Default")
      (node (ref "C2") (pin "2") (pinfunction "2_2") (pintype "passive"))
      (node (ref "C5") (pin "2") (pinfunction "2_2") (pintype "passive"))
      (node (ref "C7") (pin "+") (pinfunction "+_+") (pintype "passive"))
      (node (ref "C8") (pin "+") (pinfunction "+_+") (pintype "passive"))
      (node (ref "IC1") (pin "7") (pinfunction "V+_7") (pintype "power_in"))
      (node (ref "IC2") (pin "7") (pinfunction "V+_7") (pintype "power_in"))
      (node (ref "LED2") (pin "A") (pinfunction "A_A") (pintype "passive"))
      (node (ref "LED3") (pin "A") (pinfunction "A_A") (pintype "passive"))
      (node (ref "LED5") (pin "A") (pinfunction "A_A") (pintype "passive"))
      (node (ref "LED7") (pin "A") (pinfunction "A_A") (pintype "passive"))
      (node (ref "Q1") (pin "C") (pinfunction "C_C") (pintype "passive"))
      (node (ref "Q13") (pin "C") (pinfunction "C_C") (pintype "passive"))
      (node (ref "Q14") (pin "C") (pinfunction "C_C") (pintype "passive"))
      (node (ref "Q5") (pin "C") (pinfunction "C_C") (pintype "passive"))
      (node (ref "Q8") (pin "C") (pinfunction "C_C") (pintype "passive"))
      (node (ref "Q9") (pin "C") (pinfunction "C_C") (pintype "passive"))
      (node (ref "R1") (pin "2") (pinfunction "2_2") (pintype "passive"))
      (node (ref "R15") (pin "2") (pinfunction "2_2") (pintype "passive"))
      (node (ref "R35") (pin "2") (pinfunction "2_2") (pintype "passive"))
      (node (ref "R36") (pin "2") (pinfunction "2_2") (pintype "passive"))
      (node (ref "R43") (pin "2") (pinfunction "2_2") (pintype "passive"))
      (node (ref "X1") (pin "2") (pinfunction "KL_2") (pintype "passive"))
      (node (ref "X2") (pin "1") (pinfunction "KL_1") (pintype "passive"))
    )
    (net (code "69") (name "V-") (class "Default")
      (node (ref "C10") (pin "-") (pinfunction "-_-") (pintype "passive"))
      (node (ref "C3") (pin "1") (pinfunction "1_1") (pintype "passive"))
      (node (ref "C6") (pin "1") (pinfunction "1_1") (pintype "passive"))
      (node (ref "C9") (pin "-") (pinfunction "-_-") (pintype "passive"))
      (node (ref "IC1") (pin "4") (pinfunction "V-_4") (pintype "power_in"))
      (node (ref "IC2") (pin "4") (pinfunction "V-_4") (pintype "power_in"))
      (node (ref "LED1") (pin "C") (pinfunction "C_C") (pintype "passive"))
      (node (ref "LED4") (pin "C") (pinfunction "C_C") (pintype "passive"))
      (node (ref "LED6") (pin "C") (pinfunction "C_C") (pintype "passive"))
      (node (ref "LED8") (pin "C") (pinfunction "C_C") (pintype "passive"))
      (node (ref "Q10") (pin "C") (pinfunction "C_C") (pintype "passive"))
      (node (ref "Q15") (pin "C") (pinfunction "C_C") (pintype "passive"))
      (node (ref "Q16") (pin "C") (pinfunction "C_C") (pintype "passive"))
      (node (ref "Q2") (pin "C") (pinfunction "C_C") (pintype "passive"))
      (node (ref "Q6") (pin "C") (pinfunction "C_C") (pintype "passive"))
      (node (ref "Q7") (pin "C") (pinfunction "C_C") (pintype "passive"))
      (node (ref "R18") (pin "1") (pinfunction "1_1") (pintype "passive"))
      (node (ref "R2") (pin "1") (pinfunction "1_1") (pintype "passive"))
      (node (ref "R22") (pin "1") (pinfunction "1_1") (pintype "passive"))
      (node (ref "R23") (pin "1") (pinfunction "1_1") (pintype "passive"))
      (node (ref "R44") (pin "1") (pinfunction "1_1") (pintype "passive"))
      (node (ref "X1") (pin "1") (pinfunction "KL_1") (pintype "passive"))
      (node (ref "X2") (pin "2") (pinfunction "KL_2") (pintype "passive"))
    )
    (net (code "70") (name "unconnected-(IC1-ON1-Pad1)") (class "Default")
      (node (ref "IC1") (pin "1") (pinfunction "ON1_1") (pintype "passive"))
    )
    (net (code "71") (name "unconnected-(IC1-ON2-Pad8)") (class "Default")
      (node (ref "IC1") (pin "8") (pinfunction "ON2_8") (pintype "passive"))
    )
    (net (code "72") (name "unconnected-(IC1-OPT-Pad5)") (class "Default")
      (node (ref "IC1") (pin "5") (pinfunction "OPT_5") (pintype "passive"))
    )
    (net (code "73") (name "unconnected-(IC2-ON1-Pad1)") (class "Default")
      (node (ref "IC2") (pin "1") (pinfunction "ON1_1") (pintype "passive"))
    )
    (net (code "74") (name "unconnected-(IC2-ON2-Pad8)") (class "Default")
      (node (ref "IC2") (pin "8") (pinfunction "ON2_8") (pintype "passive"))
    )
    (net (code "75") (name "unconnected-(IC2-OPT-Pad5)") (class "Default")
      (node (ref "IC2") (pin "5") (pinfunction "OPT_5") (pintype "passive"))
    )
  )
)
